# 30_ADC.net
KiCad netlist of a schematic drawn in Altium Designer
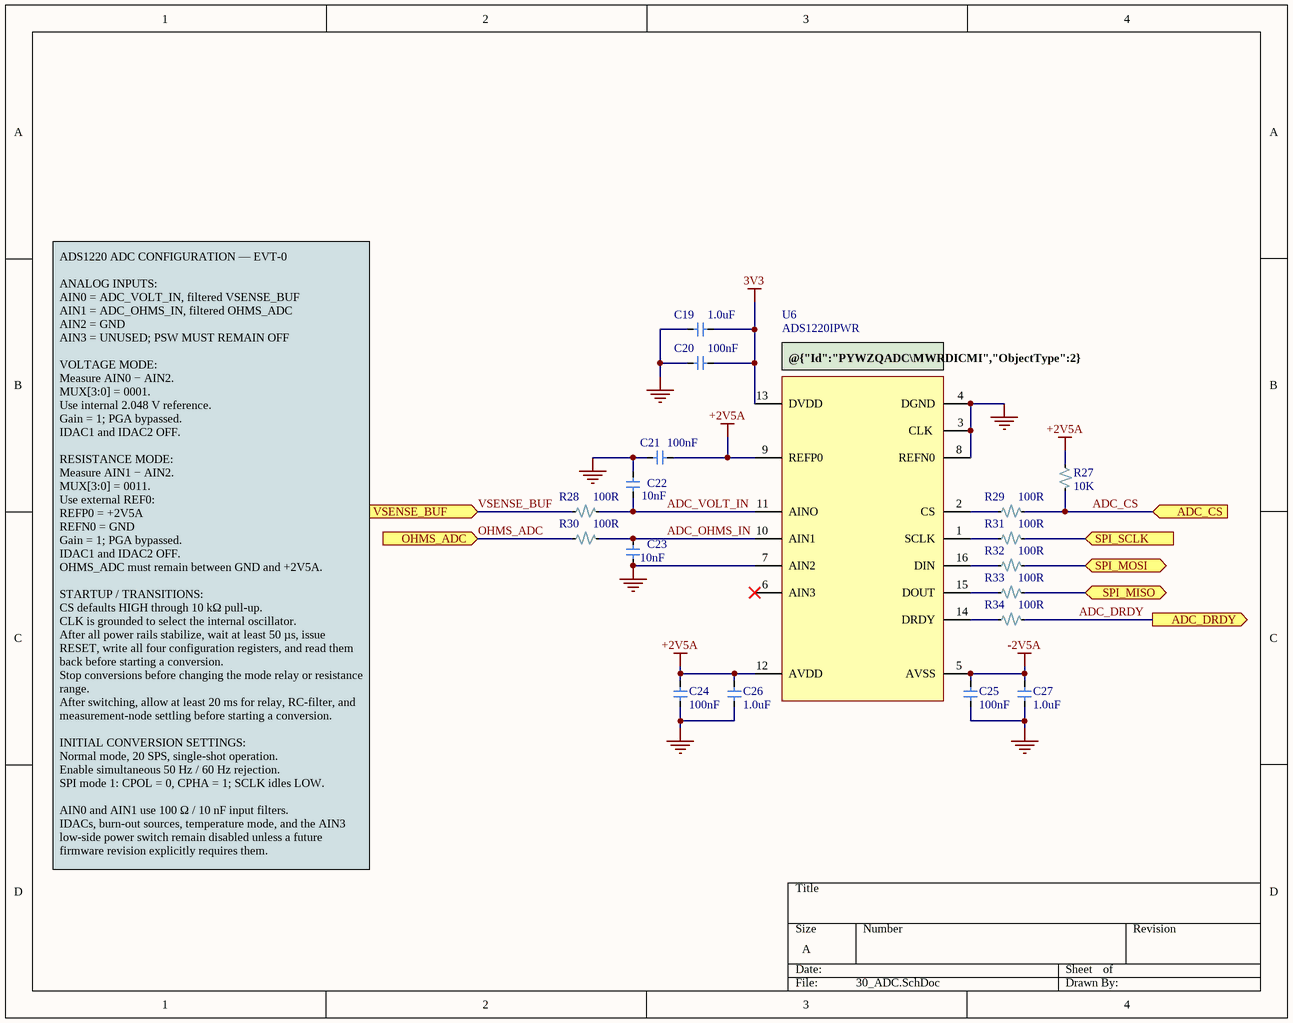
[diagram p0: 30_ADC.SchDoc]

(export (version "E")
  (design (tool "Eeschema 10.0.6"))
  (components
    (comp (ref "C19")
      (value "1.0uF")
      (footprint "C0805")
      (libsource (lib "PocketLab_DMM_SchLib") (part "C_0805"))
    )
    (comp (ref "C20")
      (value "100nF")
      (footprint "C0805")
      (libsource (lib "PocketLab_DMM_SchLib") (part "C_0805"))
    )
    (comp (ref "C21")
      (value "100nF")
      (footprint "C0805")
      (libsource (lib "PocketLab_DMM_SchLib") (part "C_0805"))
    )
    (comp (ref "C22")
      (value "10nF")
      (footprint "C0805")
      (libsource (lib "PocketLab_DMM_SchLib") (part "C_0805"))
    )
    (comp (ref "C23")
      (value "10nF")
      (footprint "C0805")
      (libsource (lib "PocketLab_DMM_SchLib") (part "C_0805"))
    )
    (comp (ref "C24")
      (value "100nF")
      (footprint "C0805")
      (libsource (lib "PocketLab_DMM_SchLib") (part "C_0805"))
    )
    (comp (ref "C25")
      (value "100nF")
      (footprint "C0805")
      (libsource (lib "PocketLab_DMM_SchLib") (part "C_0805"))
    )
    (comp (ref "C26")
      (value "1.0uF")
      (footprint "C0805")
      (libsource (lib "PocketLab_DMM_SchLib") (part "C_0805"))
    )
    (comp (ref "C27")
      (value "1.0uF")
      (footprint "C0805")
      (libsource (lib "PocketLab_DMM_SchLib") (part "C_0805"))
    )
    (comp (ref "R27")
      (value "10K")
      (footprint "R0805")
      (description "RES 1/8W 0805")
      (fields
        (field (name "MANUFACTURER") "Stackpole Electronics")
        (field (name "MANUFACTURER PART NUMBER") "RNCF0805TKY10K0")
      )
      (libsource (lib "PocketLab_DMM_EVT0") (part "R_0805"))
    )
    (comp (ref "R28")
      (value "100R")
      (footprint "R0805")
      (description "RES 1/8W 0805")
      (fields
        (field (name "MANUFACTURER") "Stackpole Electronics")
        (field (name "MANUFACTURER PART NUMBER") "RNCF0805TKY10K0")
      )
      (libsource (lib "PocketLab_DMM_EVT0") (part "R_0805"))
    )
    (comp (ref "R29")
      (value "100R")
      (footprint "R0805")
      (description "RES 1/8W 0805")
      (fields
        (field (name "MANUFACTURER") "Stackpole Electronics")
        (field (name "MANUFACTURER PART NUMBER") "RNCF0805TKY10K0")
      )
      (libsource (lib "PocketLab_DMM_EVT0") (part "R_0805"))
    )
    (comp (ref "R30")
      (value "100R")
      (footprint "R0805")
      (description "RES 1/8W 0805")
      (fields
        (field (name "MANUFACTURER") "Stackpole Electronics")
        (field (name "MANUFACTURER PART NUMBER") "RNCF0805TKY10K0")
      )
      (libsource (lib "PocketLab_DMM_EVT0") (part "R_0805"))
    )
    (comp (ref "R31")
      (value "100R")
      (footprint "R0805")
      (description "RES 1/8W 0805")
      (fields
        (field (name "MANUFACTURER") "Stackpole Electronics")
        (field (name "MANUFACTURER PART NUMBER") "RNCF0805TKY10K0")
      )
      (libsource (lib "PocketLab_DMM_EVT0") (part "R_0805"))
    )
    (comp (ref "R32")
      (value "100R")
      (footprint "R0805")
      (description "RES 1/8W 0805")
      (fields
        (field (name "MANUFACTURER") "Stackpole Electronics")
        (field (name "MANUFACTURER PART NUMBER") "RNCF0805TKY10K0")
      )
      (libsource (lib "PocketLab_DMM_EVT0") (part "R_0805"))
    )
    (comp (ref "R33")
      (value "100R")
      (footprint "R0805")
      (description "RES 1/8W 0805")
      (fields
        (field (name "MANUFACTURER") "Stackpole Electronics")
        (field (name "MANUFACTURER PART NUMBER") "RNCF0805TKY10K0")
      )
      (libsource (lib "PocketLab_DMM_EVT0") (part "R_0805"))
    )
    (comp (ref "R34")
      (value "100R")
      (footprint "R0805")
      (description "RES 1/8W 0805")
      (fields
        (field (name "MANUFACTURER") "Stackpole Electronics")
        (field (name "MANUFACTURER PART NUMBER") "RNCF0805TKY10K0")
      )
      (libsource (lib "PocketLab_DMM_EVT0") (part "R_0805"))
    )
    (comp (ref "U6")
      (value "ADS1220IPWR")
      (footprint "ADS1220IPWR")
      (description "IC ADC 24BIT 16-TSSOP")
      (fields (field (name "MANUFACTURER") "Texas Instruments"))
      (libsource (lib "PocketLab_DMM_SchLib") (part "ADS1220IPWR"))
    )
  )
  (nets
    (net (code "1") (name "+2V5A") (class "Default")
      (node (ref "C21") (pin "2") (pinfunction "2_2") (pintype "passive"))
      (node (ref "C24") (pin "2") (pinfunction "2_2") (pintype "passive"))
      (node (ref "C26") (pin "2") (pinfunction "2_2") (pintype "passive"))
      (node (ref "R27") (pin "1") (pinfunction "1_1") (pintype "passive"))
      (node (ref "U6") (pin "12") (pinfunction "AVDD_12") (pintype "passive"))
      (node (ref "U6") (pin "9") (pinfunction "REFP0_9") (pintype "passive"))
    )
    (net (code "2") (name "-2V5A") (class "Default")
      (node (ref "C25") (pin "2") (pinfunction "2_2") (pintype "passive"))
      (node (ref "C27") (pin "1") (pinfunction "1_1") (pintype "passive"))
      (node (ref "U6") (pin "5") (pinfunction "AVSS_5") (pintype "passive"))
    )
    (net (code "3") (name "/ADC_CS") (class "Default")
      (node (ref "R27") (pin "2") (pinfunction "2_2") (pintype "passive"))
      (node (ref "R29") (pin "2") (pinfunction "2_2") (pintype "passive"))
    )
    (net (code "4") (name "/ADC_DRDY") (class "Default")
      (node (ref "R34") (pin "2") (pinfunction "2_2") (pintype "passive"))
    )
    (net (code "5") (name "/ADC_OHMS_IN") (class "Default")
      (node (ref "C23") (pin "2") (pinfunction "2_2") (pintype "passive"))
      (node (ref "R30") (pin "2") (pinfunction "2_2") (pintype "passive"))
      (node (ref "U6") (pin "10") (pinfunction "AIN1_10") (pintype "passive"))
    )
    (net (code "6") (name "/ADC_VOLT_IN") (class "Default")
      (node (ref "C22") (pin "1") (pinfunction "1_1") (pintype "passive"))
      (node (ref "R28") (pin "2") (pinfunction "2_2") (pintype "passive"))
      (node (ref "U6") (pin "11") (pinfunction "AINO_11") (pintype "passive"))
    )
    (net (code "7") (name "/OHMS_ADC") (class "Default")
      (node (ref "R30") (pin "1") (pinfunction "1_1") (pintype "passive"))
    )
    (net (code "8") (name "/SPI_MISO") (class "Default")
      (node (ref "R33") (pin "2") (pinfunction "2_2") (pintype "passive"))
    )
    (net (code "9") (name "/SPI_MOSI") (class "Default")
      (node (ref "R32") (pin "2") (pinfunction "2_2") (pintype "passive"))
    )
    (net (code "10") (name "/SPI_SCLK") (class "Default")
      (node (ref "R31") (pin "2") (pinfunction "2_2") (pintype "passive"))
    )
    (net (code "11") (name "/VSENSE_BUF") (class "Default")
      (node (ref "R28") (pin "1") (pinfunction "1_1") (pintype "passive"))
    )
    (net (code "12") (name "3V3") (class "Default")
      (node (ref "C19") (pin "2") (pinfunction "2_2") (pintype "passive"))
      (node (ref "C20") (pin "2") (pinfunction "2_2") (pintype "passive"))
      (node (ref "U6") (pin "13") (pinfunction "DVDD_13") (pintype "passive"))
    )
    (net (code "13") (name "GND") (class "Default")
      (node (ref "C19") (pin "1") (pinfunction "1_1") (pintype "passive"))
      (node (ref "C20") (pin "1") (pinfunction "1_1") (pintype "passive"))
      (node (ref "C21") (pin "1") (pinfunction "1_1") (pintype "passive"))
      (node (ref "C22") (pin "2") (pinfunction "2_2") (pintype "passive"))
      (node (ref "C23") (pin "1") (pinfunction "1_1") (pintype "passive"))
      (node (ref "C24") (pin "1") (pinfunction "1_1") (pintype "passive"))
      (node (ref "C25") (pin "1") (pinfunction "1_1") (pintype "passive"))
      (node (ref "C26") (pin "1") (pinfunction "1_1") (pintype "passive"))
      (node (ref "C27") (pin "2") (pinfunction "2_2") (pintype "passive"))
      (node (ref "U6") (pin "3") (pinfunction "CLK_3") (pintype "passive"))
      (node (ref "U6") (pin "4") (pinfunction "DGND_4") (pintype "passive"))
      (node (ref "U6") (pin "7") (pinfunction "AIN2_7") (pintype "passive"))
      (node (ref "U6") (pin "8") (pinfunction "REFN0_8") (pintype "passive"))
    )
    (net (code "14") (name "Net-(U6-CS)") (class "Default")
      (node (ref "R29") (pin "1") (pinfunction "1_1") (pintype "passive"))
      (node (ref "U6") (pin "2") (pinfunction "CS_2") (pintype "passive"))
    )
    (net (code "15") (name "Net-(U6-DIN)") (class "Default")
      (node (ref "R32") (pin "1") (pinfunction "1_1") (pintype "passive"))
      (node (ref "U6") (pin "16") (pinfunction "DIN_16") (pintype "passive"))
    )
    (net (code "16") (name "Net-(U6-DOUT)") (class "Default")
      (node (ref "R33") (pin "1") (pinfunction "1_1") (pintype "passive"))
      (node (ref "U6") (pin "15") (pinfunction "DOUT_15") (pintype "passive"))
    )
    (net (code "17") (name "Net-(U6-DRDY)") (class "Default")
      (node (ref "R34") (pin "1") (pinfunction "1_1") (pintype "passive"))
      (node (ref "U6") (pin "14") (pinfunction "DRDY_14") (pintype "passive"))
    )
    (net (code "18") (name "Net-(U6-SCLK)") (class "Default")
      (node (ref "R31") (pin "1") (pinfunction "1_1") (pintype "passive"))
      (node (ref "U6") (pin "1") (pinfunction "SCLK_1") (pintype "passive"))
    )
    (net (code "19") (name "unconnected-(U6-AIN3-Pad6)") (class "Default")
      (node (ref "U6") (pin "6") (pinfunction "AIN3_6") (pintype "passive+no_connect"))
    )
  )
)
